# SetResetIC.net
KiCad netlist of a schematic drawn in Altium Designer
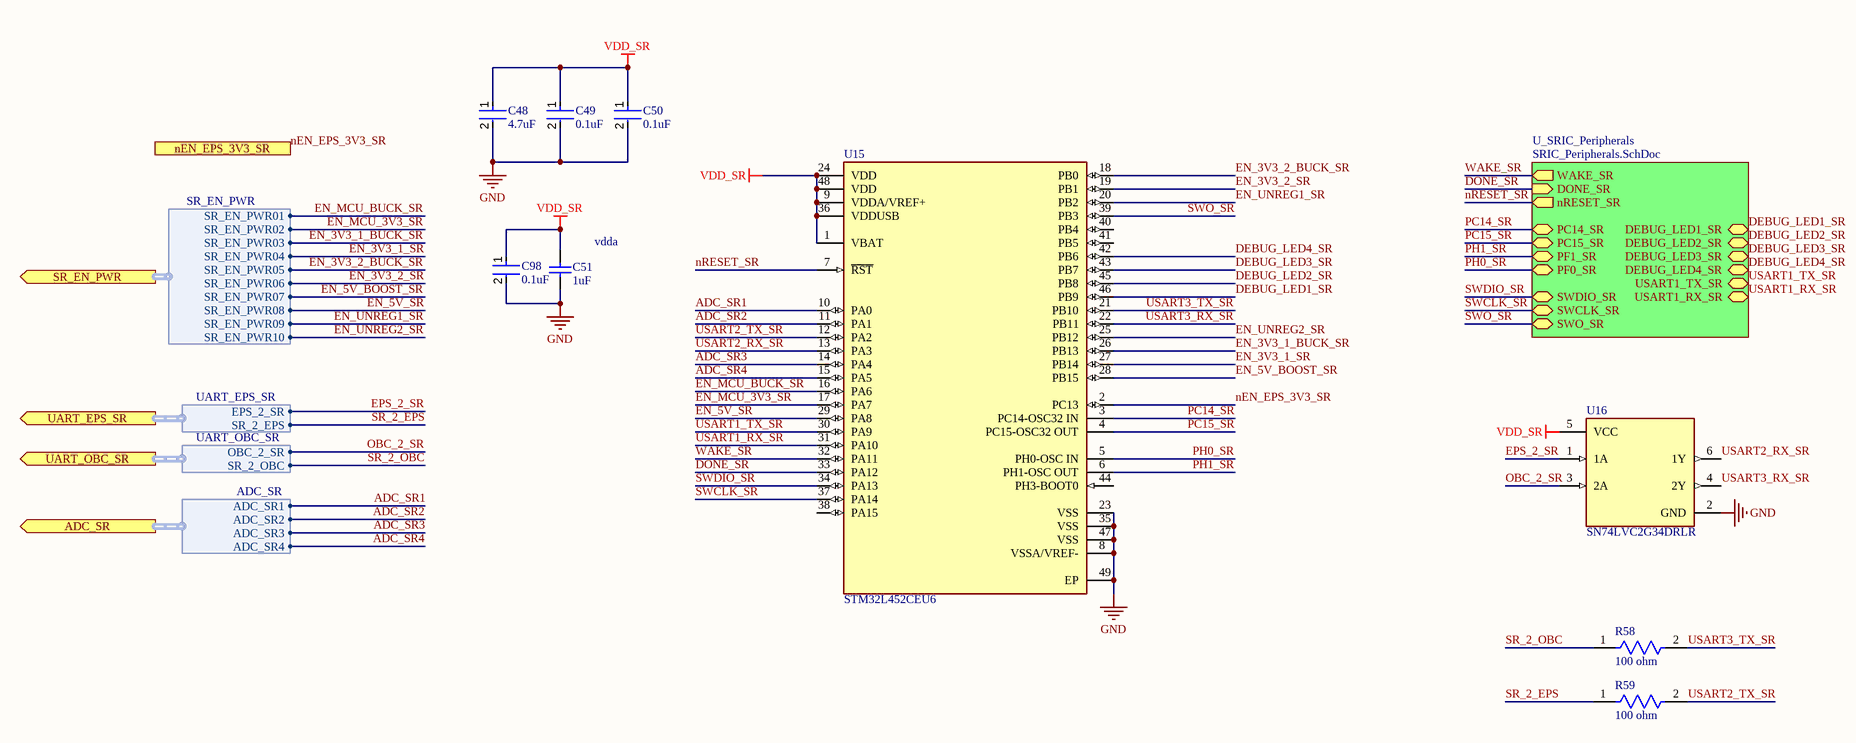
[diagram p0: SetResetIC.SchDoc]

(export (version "E")
  (design (tool "Eeschema 10.0.6"))
  (components
    (comp (ref "C48")
      (value "4.7uF")
      (footprint "FP-GRM188-0_15-IPC_A")
      (description "CAP CER 4.7UF 10V X7S 0603")
      (fields (field (name "TOLERANCE") "10%"))
      (libsource (lib "Altium Content Vault") (part "02cd4be3c70576c341d710602a673aa"))
    )
    (comp (ref "C49")
      (value "0.1uF")
      (footprint "FP-C0603C-CF-MFG")
      (description "CAP CER 0.1UF 50V X7R 0603")
      (fields (field (name "TOLERANCE") "0.1") (field (name "MANUFACTURER") "KEMET"))
      (libsource (lib "Altium Content Vault") (part "b4654b650e69147ec39a6b967a45e02"))
    )
    (comp (ref "C50")
      (value "0.1uF")
      (footprint "FP-C0603C-CF-MFG")
      (description "CAP CER 0.1UF 50V X7R 0603")
      (fields (field (name "TOLERANCE") "0.1") (field (name "MANUFACTURER") "KEMET"))
      (libsource (lib "Altium Content Vault") (part "b4654b650e69147ec39a6b967a45e02"))
    )
    (comp (ref "C51")
      (value "1uF")
      (footprint "CAPC1608X90X35ML10T15")
      (fields (field (name "PART NUMBER") "GRM188R71C105KA12J") (field (name "MANUFACTURER") "Murata"))
      (libsource (lib "Altium Content Vault") (part "CAP"))
    )
    (comp (ref "C98")
      (value "0.1uF")
      (footprint "FP-C0603C-CF-MFG")
      (description "CAP CER 0.1UF 50V X7R 0603")
      (fields (field (name "TOLERANCE") "0.1") (field (name "MANUFACTURER") "KEMET"))
      (libsource (lib "Altium Content Vault") (part "b4654b650e69147ec39a6b967a45e02"))
    )
    (comp (ref "R58")
      (value "100 ohm")
      (footprint "FP-ERJP03-MFG")
      (description "ERJ-P03F1000V SMD Chip Resistor, 100 Ohm, ± 1%, 200 mW, 0603 [1608 Metric], Thick Film, Anti-Surge")
      (fields (field (name "TOLERANCE") "1%"))
      (libsource (lib "Altium Content Vault") (part "1029c3af85768c4190bb7ad29bc67b5"))
    )
    (comp (ref "R59")
      (value "100 ohm")
      (footprint "FP-ERJP03-MFG")
      (description "ERJ-P03F1000V SMD Chip Resistor, 100 Ohm, ± 1%, 200 mW, 0603 [1608 Metric], Thick Film, Anti-Surge")
      (fields (field (name "TOLERANCE") "1%"))
      (libsource (lib "Altium Content Vault") (part "1029c3af85768c4190bb7ad29bc67b5"))
    )
    (comp (ref "U15")
      (value "STM32L452CEU6")
      (footprint "FP-UFQFPN48-A0B9-MFG")
      (description "IC MCU 32BIT 512KB FLASH 48QFPN")
      (libsource (lib "Altium Content Vault") (part "a3bdcff68b454379d220d048bba18d7"))
    )
    (comp (ref "U16")
      (value "SN74LVC2G34DRLR")
      (footprint "FP-DRL0006A-MFG")
      (description "IC BUFFER NON-INVERT 5.5V 6SOT")
      (libsource (lib "Altium Content Vault") (part "59303bce76f5fafbc101ba271662c75"))
    )
  )
  (nets
    (net (code "5") (name "/ADC_SR1") (class "Default")
      (node (ref "U15") (pin "10") (pinfunction "PA0_10") (pintype "bidirectional"))
    )
    (net (code "6") (name "/ADC_SR2") (class "Default")
      (node (ref "U15") (pin "11") (pinfunction "PA1_11") (pintype "bidirectional"))
    )
    (net (code "7") (name "/ADC_SR3") (class "Default")
      (node (ref "U15") (pin "14") (pinfunction "PA4_14") (pintype "bidirectional"))
    )
    (net (code "8") (name "/ADC_SR4") (class "Default")
      (node (ref "U15") (pin "15") (pinfunction "PA5_15") (pintype "bidirectional"))
    )
    (net (code "9") (name "/DEBUG_LED1_SR") (class "Default")
      (node (ref "U15") (pin "46") (pinfunction "PB9_46") (pintype "bidirectional"))
    )
    (net (code "10") (name "/DEBUG_LED2_SR") (class "Default")
      (node (ref "U15") (pin "45") (pinfunction "PB8_45") (pintype "bidirectional"))
    )
    (net (code "11") (name "/DEBUG_LED3_SR") (class "Default")
      (node (ref "U15") (pin "43") (pinfunction "PB7_43") (pintype "bidirectional"))
    )
    (net (code "12") (name "/DEBUG_LED4_SR") (class "Default")
      (node (ref "U15") (pin "42") (pinfunction "PB6_42") (pintype "bidirectional"))
    )
    (net (code "13") (name "/DONE_SR") (class "Default")
      (node (ref "U15") (pin "33") (pinfunction "PA12_33") (pintype "bidirectional"))
    )
    (net (code "14") (name "/EN_3V3_1_BUCK_SR") (class "Default")
      (node (ref "U15") (pin "26") (pinfunction "PB13_26") (pintype "bidirectional"))
    )
    (net (code "15") (name "/EN_3V3_1_SR") (class "Default")
      (node (ref "U15") (pin "27") (pinfunction "PB14_27") (pintype "bidirectional"))
    )
    (net (code "16") (name "/EN_3V3_2_BUCK_SR") (class "Default")
      (node (ref "U15") (pin "18") (pinfunction "PB0_18") (pintype "bidirectional"))
    )
    (net (code "17") (name "/EN_3V3_2_SR") (class "Default")
      (node (ref "U15") (pin "19") (pinfunction "PB1_19") (pintype "bidirectional"))
    )
    (net (code "18") (name "/EN_5V_BOOST_SR") (class "Default")
      (node (ref "U15") (pin "28") (pinfunction "PB15_28") (pintype "bidirectional"))
    )
    (net (code "19") (name "/EN_5V_SR") (class "Default")
      (node (ref "U15") (pin "29") (pinfunction "PA8_29") (pintype "bidirectional"))
    )
    (net (code "20") (name "/EN_MCU_3V3_SR") (class "Default")
      (node (ref "U15") (pin "17") (pinfunction "PA7_17") (pintype "bidirectional"))
    )
    (net (code "21") (name "/EN_MCU_BUCK_SR") (class "Default")
      (node (ref "U15") (pin "16") (pinfunction "PA6_16") (pintype "bidirectional"))
    )
    (net (code "22") (name "/EN_UNREG1_SR") (class "Default")
      (node (ref "U15") (pin "20") (pinfunction "PB2_20") (pintype "bidirectional"))
    )
    (net (code "23") (name "/EN_UNREG2_SR") (class "Default")
      (node (ref "U15") (pin "25") (pinfunction "PB12_25") (pintype "bidirectional"))
    )
    (net (code "24") (name "/EPS_2_SR") (class "Default")
      (node (ref "U16") (pin "1") (pinfunction "1A_1") (pintype "input"))
    )
    (net (code "25") (name "/OBC_2_SR") (class "Default")
      (node (ref "U16") (pin "3") (pinfunction "2A_3") (pintype "input"))
    )
    (net (code "26") (name "/PC14_SR") (class "Default")
      (node (ref "U15") (pin "3") (pinfunction "PC14-OSC32_IN_3") (pintype "passive"))
    )
    (net (code "27") (name "/PC15_SR") (class "Default")
      (node (ref "U15") (pin "4") (pinfunction "PC15-OSC32_OUT_4") (pintype "passive"))
    )
    (net (code "28") (name "/PH0_SR") (class "Default")
      (node (ref "U15") (pin "5") (pinfunction "PH0-OSC_IN_5") (pintype "passive"))
    )
    (net (code "29") (name "/PH1_SR") (class "Default")
      (node (ref "U15") (pin "6") (pinfunction "PH1-OSC_OUT_6") (pintype "passive"))
    )
    (net (code "30") (name "/SR_2_EPS") (class "Default")
      (node (ref "R59") (pin "1") (pinfunction "1_1") (pintype "passive"))
    )
    (net (code "31") (name "/SR_2_OBC") (class "Default")
      (node (ref "R58") (pin "1") (pinfunction "1_1") (pintype "passive"))
    )
    (net (code "32") (name "/SWCLK_SR") (class "Default")
      (node (ref "U15") (pin "37") (pinfunction "PA14_37") (pintype "bidirectional"))
    )
    (net (code "33") (name "/SWDIO_SR") (class "Default")
      (node (ref "U15") (pin "34") (pinfunction "PA13_34") (pintype "bidirectional"))
    )
    (net (code "34") (name "/SWO_SR") (class "Default")
      (node (ref "U15") (pin "39") (pinfunction "PB3_39") (pintype "bidirectional"))
    )
    (net (code "35") (name "/USART1_RX_SR") (class "Default")
      (node (ref "U15") (pin "31") (pinfunction "PA10_31") (pintype "bidirectional"))
    )
    (net (code "36") (name "/USART1_TX_SR") (class "Default")
      (node (ref "U15") (pin "30") (pinfunction "PA9_30") (pintype "bidirectional"))
    )
    (net (code "37") (name "/USART2_RX_SR") (class "Default")
      (node (ref "U15") (pin "13") (pinfunction "PA3_13") (pintype "bidirectional"))
      (node (ref "U16") (pin "6") (pinfunction "1Y_6") (pintype "output"))
    )
    (net (code "38") (name "/USART2_TX_SR") (class "Default")
      (node (ref "R59") (pin "2") (pinfunction "2_2") (pintype "passive"))
      (node (ref "U15") (pin "12") (pinfunction "PA2_12") (pintype "bidirectional"))
    )
    (net (code "39") (name "/USART3_RX_SR") (class "Default")
      (node (ref "U15") (pin "22") (pinfunction "PB11_22") (pintype "bidirectional"))
      (node (ref "U16") (pin "4") (pinfunction "2Y_4") (pintype "output"))
    )
    (net (code "40") (name "/USART3_TX_SR") (class "Default")
      (node (ref "R58") (pin "2") (pinfunction "2_2") (pintype "passive"))
      (node (ref "U15") (pin "21") (pinfunction "PB10_21") (pintype "bidirectional"))
    )
    (net (code "41") (name "/WAKE_SR") (class "Default")
      (node (ref "U15") (pin "32") (pinfunction "PA11_32") (pintype "bidirectional"))
    )
    (net (code "42") (name "/nEN_EPS_3V3_SR") (class "Default")
      (node (ref "U15") (pin "2") (pinfunction "PC13_2") (pintype "bidirectional"))
    )
    (net (code "43") (name "/nRESET_SR") (class "Default")
      (node (ref "U15") (pin "7") (pinfunction "~{RST}_7") (pintype "input"))
    )
    (net (code "48") (name "GND") (class "Default")
      (node (ref "C48") (pin "2") (pinfunction "2_2") (pintype "passive"))
      (node (ref "C49") (pin "2") (pinfunction "2_2") (pintype "passive"))
      (node (ref "C50") (pin "2") (pinfunction "2_2") (pintype "passive"))
      (node (ref "C51") (pin "1") (pinfunction "1_1") (pintype "passive"))
      (node (ref "C98") (pin "2") (pinfunction "2_2") (pintype "passive"))
      (node (ref "U15") (pin "23") (pinfunction "VSS_23") (pintype "power_in"))
      (node (ref "U15") (pin "35") (pinfunction "VSS_35") (pintype "power_in"))
      (node (ref "U15") (pin "47") (pinfunction "VSS_47") (pintype "power_in"))
      (node (ref "U15") (pin "49") (pinfunction "EP_49") (pintype "power_in"))
      (node (ref "U15") (pin "8") (pinfunction "VSSA/VREF-_8") (pintype "power_in"))
      (node (ref "U16") (pin "2") (pinfunction "GND_2") (pintype "power_in"))
    )
    (net (code "49") (name "VDD_SR") (class "Default")
      (node (ref "C48") (pin "1") (pinfunction "1_1") (pintype "passive"))
      (node (ref "C49") (pin "1") (pinfunction "1_1") (pintype "passive"))
      (node (ref "C50") (pin "1") (pinfunction "1_1") (pintype "passive"))
      (node (ref "C51") (pin "2") (pinfunction "2_2") (pintype "passive"))
      (node (ref "C98") (pin "1") (pinfunction "1_1") (pintype "passive"))
      (node (ref "U15") (pin "1") (pinfunction "VBAT_1") (pintype "power_in"))
      (node (ref "U15") (pin "24") (pinfunction "VDD_24") (pintype "power_in"))
      (node (ref "U15") (pin "36") (pinfunction "VDDUSB_36") (pintype "power_in"))
      (node (ref "U15") (pin "48") (pinfunction "VDD_48") (pintype "power_in"))
      (node (ref "U15") (pin "9") (pinfunction "VDDA/VREF+_9") (pintype "power_in"))
      (node (ref "U16") (pin "5") (pinfunction "VCC_5") (pintype "power_in"))
    )
    (net (code "50") (name "unconnected-(U15-PA15-Pad38)") (class "Default")
      (node (ref "U15") (pin "38") (pinfunction "PA15_38") (pintype "bidirectional"))
    )
    (net (code "51") (name "unconnected-(U15-PB4-Pad40)") (class "Default")
      (node (ref "U15") (pin "40") (pinfunction "PB4_40") (pintype "bidirectional"))
    )
    (net (code "52") (name "unconnected-(U15-PB5-Pad41)") (class "Default")
      (node (ref "U15") (pin "41") (pinfunction "PB5_41") (pintype "bidirectional"))
    )
    (net (code "53") (name "unconnected-(U15-PH3-BOOT0-Pad44)") (class "Default")
      (node (ref "U15") (pin "44") (pinfunction "PH3-BOOT0_44") (pintype "input"))
    )
  )
)
